# main_v2.net
KiCad netlist of a schematic drawn in EAGLE
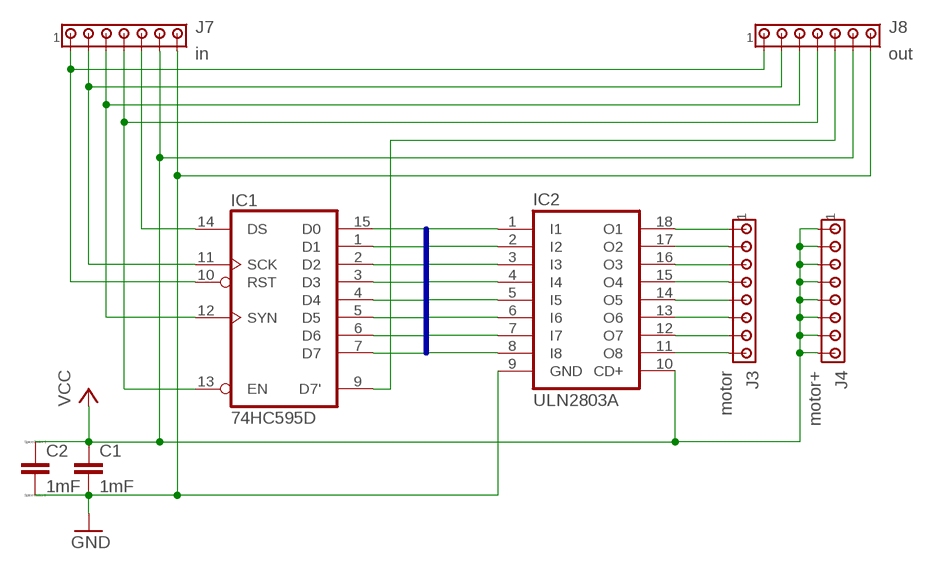
[diagram p0: schematic, sheet 1]

(export (version "E")
  (design (tool "Eeschema 10.0.6"))
  (components
    (comp (ref "C1")
      (value "1mF")
      (footprint "eagle-import:C5B2.5")
      (libsource (lib "eagle-import") (part "C5/2.5"))
    )
    (comp (ref "C2")
      (value "1mF")
      (footprint "eagle-import:C0402")
      (libsource (lib "eagle-import") (part "CC0402"))
    )
    (comp (ref "IC1")
      (value "74HC595D")
      (footprint "eagle-import:SO16")
      (libsource (lib "eagle-import") (part "74595DHC"))
    )
    (comp (ref "IC2")
      (value "ULN2803A")
      (footprint "eagle-import:SO18W")
      (libsource (lib "eagle-import") (part "ULN2803ASO18W"))
    )
    (comp (ref "J3")
      (value "motor")
      (footprint "eagle-import:10X08MTA")
      (libsource (lib "eagle-import") (part "MTA08-100"))
    )
    (comp (ref "J4")
      (value "motor+")
      (footprint "eagle-import:10X08MTA")
      (libsource (lib "eagle-import") (part "MTA08-100"))
    )
    (comp (ref "J7")
      (value "in")
      (footprint "eagle-import:10X07MTA")
      (libsource (lib "eagle-import") (part "MTA07-100"))
    )
    (comp (ref "J8")
      (value "out")
      (footprint "eagle-import:10X07MTA")
      (libsource (lib "eagle-import") (part "MTA07-100"))
    )
  )
  (nets
    (net (code "1") (name "/D1") (class "Default")
      (node (ref "IC1") (pin "15") (pinfunction "D0_15") (pintype "tri_state"))
      (node (ref "IC2") (pin "8") (pinfunction "I8_8") (pintype "input"))
    )
    (net (code "2") (name "/D2") (class "Default")
      (node (ref "IC1") (pin "1") (pinfunction "D1_1") (pintype "tri_state"))
      (node (ref "IC2") (pin "7") (pinfunction "I7_7") (pintype "input"))
    )
    (net (code "3") (name "/D3") (class "Default")
      (node (ref "IC1") (pin "2") (pinfunction "D2_2") (pintype "tri_state"))
      (node (ref "IC2") (pin "6") (pinfunction "I6_6") (pintype "input"))
    )
    (net (code "4") (name "/D4") (class "Default")
      (node (ref "IC1") (pin "3") (pinfunction "D3_3") (pintype "tri_state"))
      (node (ref "IC2") (pin "5") (pinfunction "I5_5") (pintype "input"))
    )
    (net (code "5") (name "/D5") (class "Default")
      (node (ref "IC1") (pin "4") (pinfunction "D4_4") (pintype "tri_state"))
      (node (ref "IC2") (pin "4") (pinfunction "I4_4") (pintype "input"))
    )
    (net (code "6") (name "/D6") (class "Default")
      (node (ref "IC1") (pin "5") (pinfunction "D5_5") (pintype "tri_state"))
      (node (ref "IC2") (pin "3") (pinfunction "I3_3") (pintype "input"))
    )
    (net (code "7") (name "/D7") (class "Default")
      (node (ref "IC1") (pin "6") (pinfunction "D6_6") (pintype "tri_state"))
      (node (ref "IC2") (pin "2") (pinfunction "I2_2") (pintype "input"))
    )
    (net (code "8") (name "/D8") (class "Default")
      (node (ref "IC1") (pin "7") (pinfunction "D7_7") (pintype "tri_state"))
      (node (ref "IC2") (pin "1") (pinfunction "I1_1") (pintype "input"))
    )
    (net (code "9") (name "GND") (class "Default")
      (node (ref "C1") (pin "2") (pinfunction "2_2") (pintype "passive"))
      (node (ref "C2") (pin "2") (pinfunction "2_2") (pintype "passive"))
      (node (ref "IC2") (pin "9") (pinfunction "GND_9") (pintype "power_in"))
      (node (ref "J7") (pin "7") (pinfunction "7_7") (pintype "passive"))
      (node (ref "J8") (pin "7") (pinfunction "7_7") (pintype "passive"))
    )
    (net (code "10") (name "Net-(IC1A-D7')") (class "Default")
      (node (ref "IC1") (pin "9") (pinfunction "D7'_9") (pintype "tri_state"))
      (node (ref "J8") (pin "5") (pinfunction "5_5") (pintype "passive"))
    )
    (net (code "11") (name "Net-(IC1A-DS)") (class "Default")
      (node (ref "IC1") (pin "14") (pinfunction "DS_14") (pintype "input"))
      (node (ref "J7") (pin "5") (pinfunction "5_5") (pintype "passive"))
    )
    (net (code "12") (name "Net-(IC1A-EN)") (class "Default")
      (node (ref "IC1") (pin "13") (pinfunction "EN_13") (pintype "input"))
      (node (ref "J7") (pin "4") (pinfunction "4_4") (pintype "passive"))
      (node (ref "J8") (pin "4") (pinfunction "4_4") (pintype "passive"))
    )
    (net (code "13") (name "Net-(IC1A-RST)") (class "Default")
      (node (ref "IC1") (pin "10") (pinfunction "RST_10") (pintype "input"))
      (node (ref "J7") (pin "1") (pinfunction "1_1") (pintype "passive"))
      (node (ref "J8") (pin "1") (pinfunction "1_1") (pintype "passive"))
    )
    (net (code "14") (name "Net-(IC1A-SCK)") (class "Default")
      (node (ref "IC1") (pin "11") (pinfunction "SCK_11") (pintype "input"))
      (node (ref "J7") (pin "2") (pinfunction "2_2") (pintype "passive"))
      (node (ref "J8") (pin "2") (pinfunction "2_2") (pintype "passive"))
    )
    (net (code "15") (name "Net-(IC1A-SYN)") (class "Default")
      (node (ref "IC1") (pin "12") (pinfunction "SYN_12") (pintype "input"))
      (node (ref "J7") (pin "3") (pinfunction "3_3") (pintype "passive"))
      (node (ref "J8") (pin "3") (pinfunction "3_3") (pintype "passive"))
    )
    (net (code "16") (name "Net-(IC2-O1)") (class "Default")
      (node (ref "IC2") (pin "18") (pinfunction "O1_18") (pintype "open_collector"))
      (node (ref "J3") (pin "1") (pinfunction "1_1") (pintype "passive"))
    )
    (net (code "17") (name "Net-(IC2-O2)") (class "Default")
      (node (ref "IC2") (pin "17") (pinfunction "O2_17") (pintype "open_collector"))
      (node (ref "J3") (pin "2") (pinfunction "2_2") (pintype "passive"))
    )
    (net (code "18") (name "Net-(IC2-O3)") (class "Default")
      (node (ref "IC2") (pin "16") (pinfunction "O3_16") (pintype "open_collector"))
      (node (ref "J3") (pin "3") (pinfunction "3_3") (pintype "passive"))
    )
    (net (code "19") (name "Net-(IC2-O4)") (class "Default")
      (node (ref "IC2") (pin "15") (pinfunction "O4_15") (pintype "open_collector"))
      (node (ref "J3") (pin "4") (pinfunction "4_4") (pintype "passive"))
    )
    (net (code "20") (name "Net-(IC2-O5)") (class "Default")
      (node (ref "IC2") (pin "14") (pinfunction "O5_14") (pintype "open_collector"))
      (node (ref "J3") (pin "5") (pinfunction "5_5") (pintype "passive"))
    )
    (net (code "21") (name "Net-(IC2-O6)") (class "Default")
      (node (ref "IC2") (pin "13") (pinfunction "O6_13") (pintype "open_collector"))
      (node (ref "J3") (pin "6") (pinfunction "6_6") (pintype "passive"))
    )
    (net (code "22") (name "Net-(IC2-O7)") (class "Default")
      (node (ref "IC2") (pin "12") (pinfunction "O7_12") (pintype "open_collector"))
      (node (ref "J3") (pin "7") (pinfunction "7_7") (pintype "passive"))
    )
    (net (code "23") (name "Net-(IC2-O8)") (class "Default")
      (node (ref "IC2") (pin "11") (pinfunction "O8_11") (pintype "open_collector"))
      (node (ref "J3") (pin "8") (pinfunction "8_8") (pintype "passive"))
    )
    (net (code "24") (name "VCC") (class "Default")
      (node (ref "C1") (pin "1") (pinfunction "1_1") (pintype "passive"))
      (node (ref "C2") (pin "1") (pinfunction "1_1") (pintype "passive"))
      (node (ref "IC2") (pin "10") (pinfunction "CD+_10") (pintype "passive"))
      (node (ref "J4") (pin "1") (pinfunction "1_1") (pintype "passive"))
      (node (ref "J4") (pin "2") (pinfunction "2_2") (pintype "passive"))
      (node (ref "J4") (pin "3") (pinfunction "3_3") (pintype "passive"))
      (node (ref "J4") (pin "4") (pinfunction "4_4") (pintype "passive"))
      (node (ref "J4") (pin "5") (pinfunction "5_5") (pintype "passive"))
      (node (ref "J4") (pin "6") (pinfunction "6_6") (pintype "passive"))
      (node (ref "J4") (pin "7") (pinfunction "7_7") (pintype "passive"))
      (node (ref "J4") (pin "8") (pinfunction "8_8") (pintype "passive"))
      (node (ref "J7") (pin "6") (pinfunction "6_6") (pintype "passive"))
      (node (ref "J8") (pin "6") (pinfunction "6_6") (pintype "passive"))
    )
  )
)
